# adpicd2.net
KiCad netlist of a schematic drawn in EAGLE
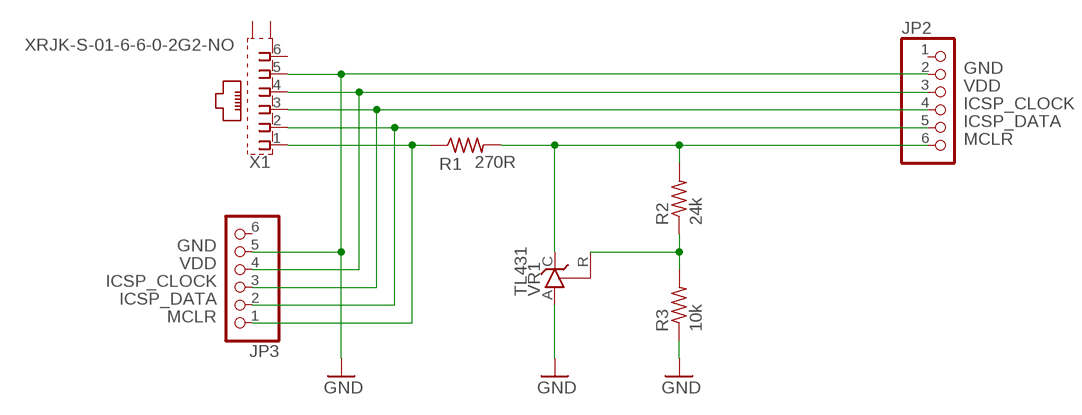
[diagram p0: schematic, sheet 1]

(export (version "E")
  (design (tool "Eeschema 10.0.6"))
  (components
    (comp (ref "JP2")
      (value "PINHD-1X6")
      (footprint "eagle-import:1X06")
      (libsource (lib "eagle-import") (part "PINHD-1X6"))
    )
    (comp (ref "JP3")
      (value "PINHD-1X6")
      (footprint "eagle-import:1X06")
      (libsource (lib "eagle-import") (part "PINHD-1X6"))
    )
    (comp (ref "R1")
      (value "270R")
      (footprint "eagle-import:0204_5")
      (libsource (lib "eagle-import") (part "R-US_0204/5"))
    )
    (comp (ref "R2")
      (value "24k")
      (footprint "eagle-import:0204_5")
      (libsource (lib "eagle-import") (part "R-US_0204/5"))
    )
    (comp (ref "R3")
      (value "10k")
      (footprint "eagle-import:0204_5")
      (libsource (lib "eagle-import") (part "R-US_0204/5"))
    )
    (comp (ref "VR1")
      (value "TL431")
      (footprint "eagle-import:TO92-CLP")
      (libsource (lib "eagle-import") (part "TL431CLP"))
    )
    (comp (ref "X1")
      (value "XRJK-S-01-6-6-0-2G2-NO")
      (footprint "eagle-import:XRJK-S-01-6-6-0-2G2-NO")
      (libsource (lib "eagle-import") (part "XRJK6-0-2G2-NO-S-01-6-"))
    )
  )
  (nets
    (net (code "1") (name "GND") (class "Default")
      (node (ref "JP2") (pin "2") (pinfunction "2_2") (pintype "passive"))
      (node (ref "JP3") (pin "5") (pinfunction "5_5") (pintype "passive"))
      (node (ref "R3") (pin "1") (pinfunction "1_1") (pintype "passive"))
      (node (ref "VR1") (pin "A") (pinfunction "A_A") (pintype "passive"))
      (node (ref "X1") (pin "5") (pinfunction "5_5") (pintype "passive"))
    )
    (net (code "2") (name "Net-(JP2-Pad3)") (class "Default")
      (node (ref "JP2") (pin "3") (pinfunction "3_3") (pintype "passive"))
      (node (ref "JP3") (pin "4") (pinfunction "4_4") (pintype "passive"))
      (node (ref "X1") (pin "4") (pinfunction "4_4") (pintype "passive"))
    )
    (net (code "3") (name "Net-(JP2-Pad4)") (class "Default")
      (node (ref "JP2") (pin "4") (pinfunction "4_4") (pintype "passive"))
      (node (ref "JP3") (pin "3") (pinfunction "3_3") (pintype "passive"))
      (node (ref "X1") (pin "3") (pinfunction "3_3") (pintype "passive"))
    )
    (net (code "4") (name "Net-(JP2-Pad5)") (class "Default")
      (node (ref "JP2") (pin "5") (pinfunction "5_5") (pintype "passive"))
      (node (ref "JP3") (pin "2") (pinfunction "2_2") (pintype "passive"))
      (node (ref "X1") (pin "2") (pinfunction "2_2") (pintype "passive"))
    )
    (net (code "5") (name "Net-(JP2-Pad6)") (class "Default")
      (node (ref "JP2") (pin "6") (pinfunction "6_6") (pintype "passive"))
      (node (ref "R1") (pin "2") (pinfunction "2_2") (pintype "passive"))
      (node (ref "R2") (pin "2") (pinfunction "2_2") (pintype "passive"))
      (node (ref "VR1") (pin "C") (pinfunction "C_C") (pintype "passive"))
    )
    (net (code "6") (name "Net-(JP3-Pad1)") (class "Default")
      (node (ref "JP3") (pin "1") (pinfunction "1_1") (pintype "passive"))
      (node (ref "R1") (pin "1") (pinfunction "1_1") (pintype "passive"))
      (node (ref "X1") (pin "1") (pinfunction "1_1") (pintype "passive"))
    )
    (net (code "7") (name "Net-(R2-Pad1)") (class "Default")
      (node (ref "R2") (pin "1") (pinfunction "1_1") (pintype "passive"))
      (node (ref "R3") (pin "2") (pinfunction "2_2") (pintype "passive"))
      (node (ref "VR1") (pin "R") (pinfunction "R_R") (pintype "passive"))
    )
    (net (code "8") (name "unconnected-(JP2-Pad1)") (class "Default")
      (node (ref "JP2") (pin "1") (pinfunction "1_1") (pintype "passive"))
    )
    (net (code "9") (name "unconnected-(JP3-Pad6)") (class "Default")
      (node (ref "JP3") (pin "6") (pinfunction "6_6") (pintype "passive"))
    )
    (net (code "10") (name "unconnected-(X1-Pad6)") (class "Default")
      (node (ref "X1") (pin "6") (pinfunction "6_6") (pintype "passive"))
    )
    (net (code "11") (name "unconnected-(X1-S-PadS1)") (class "Default")
      (node (ref "X1") (pin "S1") (pinfunction "S_S1") (pintype "passive"))
    )
    (net (code "12") (name "unconnected-(X1-S-PadS2)") (class "Default")
      (node (ref "X1") (pin "S2") (pinfunction "S_S2") (pintype "passive"))
    )
  )
)
